# diagram.net
KiCad netlist of a schematic drawn in EAGLE
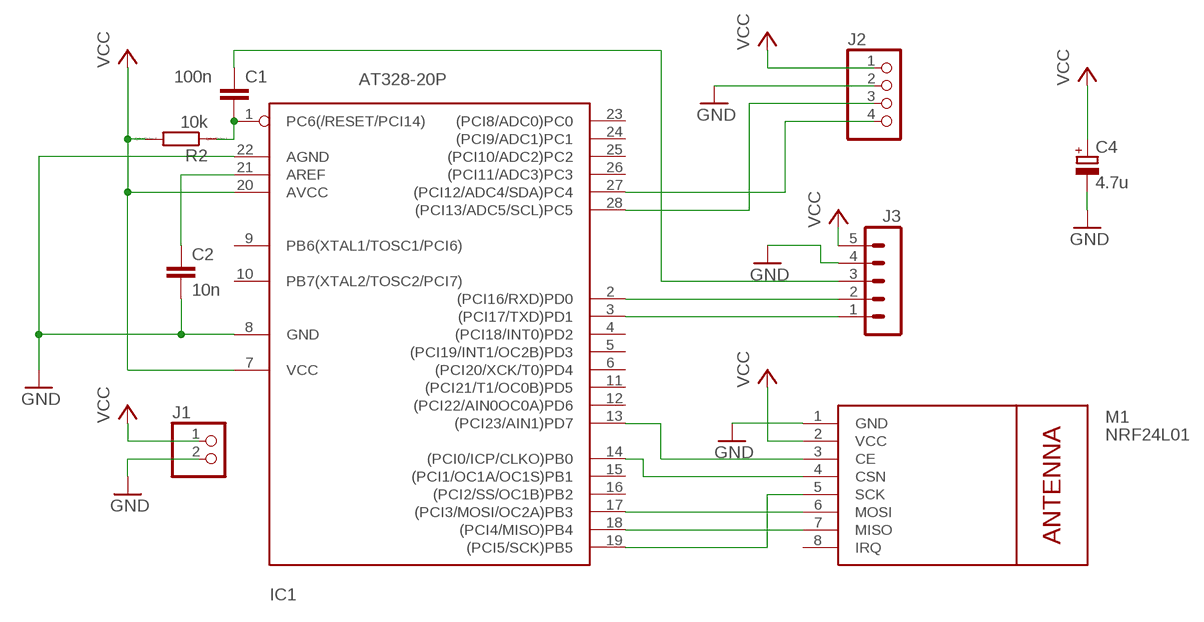
[diagram p0: schematic, sheet 1]

(export (version "E")
  (design (tool "Eeschema 10.0.6"))
  (components
    (comp (ref "C1")
      (value "100n")
      (footprint "eagle-import:C050-024X044")
      (libsource (lib "eagle-import") (part "C-EU050-024X044"))
    )
    (comp (ref "C2")
      (value "10n")
      (footprint "eagle-import:C050-024X044")
      (libsource (lib "eagle-import") (part "C-EU050-024X044"))
    )
    (comp (ref "C4")
      (value "4.7u")
      (footprint "eagle-import:E1,8-4")
      (libsource (lib "eagle-import") (part "CPOL-EUE1.8-4"))
    )
    (comp (ref "IC1")
      (value "AT328-20P")
      (footprint "eagle-import:DIL28-3")
      (libsource (lib "eagle-import") (part "ATMEGA328P-20"))
    )
    (comp (ref "J1")
      (value "PINHD-1X2")
      (footprint "eagle-import:1X02")
      (libsource (lib "eagle-import") (part "PINHD-1X2"))
    )
    (comp (ref "J2")
      (value "PINHD-1X4")
      (footprint "eagle-import:1X04")
      (libsource (lib "eagle-import") (part "PINHD-1X4"))
    )
    (comp (ref "J3")
      (value "MA05-1")
      (footprint "eagle-import:MA05-1")
      (libsource (lib "eagle-import") (part "MA05-1"))
    )
    (comp (ref "M1")
      (value "NRF24L01")
      (footprint "eagle-import:WIRELESS-NRF24L01")
      (libsource (lib "eagle-import") (part "WIRELESS-NRF24L01"))
    )
    (comp (ref "R2")
      (value "10k")
      (footprint "eagle-import:0204_7")
      (libsource (lib "eagle-import") (part "R0204/7"))
    )
  )
  (nets
    (net (code "1") (name "GND") (class "Default")
      (node (ref "C2") (pin "2") (pinfunction "2_2") (pintype "passive"))
      (node (ref "C4") (pin "-") (pinfunction "-_-") (pintype "passive"))
      (node (ref "IC1") (pin "22") (pinfunction "AGND_22") (pintype "bidirectional"))
      (node (ref "IC1") (pin "8") (pinfunction "GND_8") (pintype "bidirectional"))
      (node (ref "J1") (pin "2") (pinfunction "2_2") (pintype "passive"))
      (node (ref "J2") (pin "2") (pinfunction "2_2") (pintype "passive"))
      (node (ref "J3") (pin "4") (pinfunction "4_4") (pintype "passive"))
      (node (ref "M1") (pin "1") (pinfunction "GND_1") (pintype "power_in"))
    )
    (net (code "2") (name "Net-(C1-Pad1)") (class "Default")
      (node (ref "C1") (pin "1") (pinfunction "1_1") (pintype "passive"))
      (node (ref "J3") (pin "3") (pinfunction "3_3") (pintype "passive"))
    )
    (net (code "3") (name "Net-(IC1-(PCI0{slash}ICP{slash}CLKO)PB0)") (class "Default")
      (node (ref "IC1") (pin "14") (pinfunction "(PCI0/ICP/CLKO)PB0_14") (pintype "bidirectional"))
      (node (ref "M1") (pin "4") (pinfunction "CSN_4") (pintype "bidirectional"))
    )
    (net (code "4") (name "Net-(IC1-(PCI3{slash}MOSI{slash}OC2A)PB3)") (class "Default")
      (node (ref "IC1") (pin "17") (pinfunction "(PCI3/MOSI/OC2A)PB3_17") (pintype "bidirectional"))
      (node (ref "M1") (pin "6") (pinfunction "MOSI_6") (pintype "bidirectional"))
    )
    (net (code "5") (name "Net-(IC1-(PCI4{slash}MISO)PB4)") (class "Default")
      (node (ref "IC1") (pin "18") (pinfunction "(PCI4/MISO)PB4_18") (pintype "bidirectional"))
      (node (ref "M1") (pin "7") (pinfunction "MISO_7") (pintype "bidirectional"))
    )
    (net (code "6") (name "Net-(IC1-(PCI5{slash}SCK)PB5)") (class "Default")
      (node (ref "IC1") (pin "19") (pinfunction "(PCI5/SCK)PB5_19") (pintype "bidirectional"))
      (node (ref "M1") (pin "5") (pinfunction "SCK_5") (pintype "bidirectional"))
    )
    (net (code "7") (name "Net-(IC1-(PCI12{slash}ADC4{slash}SDA)PC4)") (class "Default")
      (node (ref "IC1") (pin "27") (pinfunction "(PCI12/ADC4/SDA)PC4_27") (pintype "bidirectional"))
      (node (ref "J2") (pin "4") (pinfunction "4_4") (pintype "passive"))
    )
    (net (code "8") (name "Net-(IC1-(PCI13{slash}ADC5{slash}SCL)PC5)") (class "Default")
      (node (ref "IC1") (pin "28") (pinfunction "(PCI13/ADC5/SCL)PC5_28") (pintype "bidirectional"))
      (node (ref "J2") (pin "3") (pinfunction "3_3") (pintype "passive"))
    )
    (net (code "9") (name "Net-(IC1-(PCI16{slash}RXD)PD0)") (class "Default")
      (node (ref "IC1") (pin "2") (pinfunction "(PCI16/RXD)PD0_2") (pintype "bidirectional"))
      (node (ref "J3") (pin "2") (pinfunction "2_2") (pintype "passive"))
    )
    (net (code "10") (name "Net-(IC1-(PCI17{slash}TXD)PD1)") (class "Default")
      (node (ref "IC1") (pin "3") (pinfunction "(PCI17/TXD)PD1_3") (pintype "bidirectional"))
      (node (ref "J3") (pin "1") (pinfunction "1_1") (pintype "passive"))
    )
    (net (code "11") (name "Net-(IC1-(PCI23{slash}AIN1)PD7)") (class "Default")
      (node (ref "IC1") (pin "13") (pinfunction "(PCI23/AIN1)PD7_13") (pintype "bidirectional"))
      (node (ref "M1") (pin "3") (pinfunction "CE_3") (pintype "bidirectional"))
    )
    (net (code "12") (name "Net-(IC1-AREF)") (class "Default")
      (node (ref "C2") (pin "1") (pinfunction "1_1") (pintype "passive"))
      (node (ref "IC1") (pin "21") (pinfunction "AREF_21") (pintype "bidirectional"))
    )
    (net (code "13") (name "Net-(IC1-PC6({slash}RESET{slash}PCI14))") (class "Default")
      (node (ref "C1") (pin "2") (pinfunction "2_2") (pintype "passive"))
      (node (ref "IC1") (pin "1") (pinfunction "PC6(/RESET/PCI14)_1") (pintype "bidirectional"))
      (node (ref "R2") (pin "1") (pinfunction "1_1") (pintype "passive"))
    )
    (net (code "14") (name "VCC") (class "Default")
      (node (ref "C4") (pin "+") (pinfunction "+_+") (pintype "passive"))
      (node (ref "IC1") (pin "20") (pinfunction "AVCC_20") (pintype "bidirectional"))
      (node (ref "IC1") (pin "7") (pinfunction "VCC_7") (pintype "bidirectional"))
      (node (ref "J1") (pin "1") (pinfunction "1_1") (pintype "passive"))
      (node (ref "J2") (pin "1") (pinfunction "1_1") (pintype "passive"))
      (node (ref "J3") (pin "5") (pinfunction "5_5") (pintype "passive"))
      (node (ref "M1") (pin "2") (pinfunction "VCC_2") (pintype "power_in"))
      (node (ref "R2") (pin "2") (pinfunction "2_2") (pintype "passive"))
    )
    (net (code "15") (name "unconnected-(IC1-(PCI1{slash}OC1A{slash}OC1S)PB1-Pad15)") (class "Default")
      (node (ref "IC1") (pin "15") (pinfunction "(PCI1/OC1A/OC1S)PB1_15") (pintype "bidirectional"))
    )
    (net (code "16") (name "unconnected-(IC1-(PCI2{slash}SS{slash}OC1B)PB2-Pad16)") (class "Default")
      (node (ref "IC1") (pin "16") (pinfunction "(PCI2/SS/OC1B)PB2_16") (pintype "bidirectional"))
    )
    (net (code "17") (name "unconnected-(IC1-(PCI8{slash}ADC0)PC0-Pad23)") (class "Default")
      (node (ref "IC1") (pin "23") (pinfunction "(PCI8/ADC0)PC0_23") (pintype "bidirectional"))
    )
    (net (code "18") (name "unconnected-(IC1-(PCI9{slash}ADC1)PC1-Pad24)") (class "Default")
      (node (ref "IC1") (pin "24") (pinfunction "(PCI9/ADC1)PC1_24") (pintype "bidirectional"))
    )
    (net (code "19") (name "unconnected-(IC1-(PCI10{slash}ADC2)PC2-Pad25)") (class "Default")
      (node (ref "IC1") (pin "25") (pinfunction "(PCI10/ADC2)PC2_25") (pintype "bidirectional"))
    )
    (net (code "20") (name "unconnected-(IC1-(PCI11{slash}ADC3)PC3-Pad26)") (class "Default")
      (node (ref "IC1") (pin "26") (pinfunction "(PCI11/ADC3)PC3_26") (pintype "bidirectional"))
    )
    (net (code "21") (name "unconnected-(IC1-(PCI18{slash}INT0)PD2-Pad4)") (class "Default")
      (node (ref "IC1") (pin "4") (pinfunction "(PCI18/INT0)PD2_4") (pintype "bidirectional"))
    )
    (net (code "22") (name "unconnected-(IC1-(PCI19{slash}INT1{slash}OC2B)PD3-Pad5)") (class "Default")
      (node (ref "IC1") (pin "5") (pinfunction "(PCI19/INT1/OC2B)PD3_5") (pintype "bidirectional"))
    )
    (net (code "23") (name "unconnected-(IC1-(PCI20{slash}XCK{slash}T0)PD4-Pad6)") (class "Default")
      (node (ref "IC1") (pin "6") (pinfunction "(PCI20/XCK/T0)PD4_6") (pintype "bidirectional"))
    )
    (net (code "24") (name "unconnected-(IC1-(PCI21{slash}T1{slash}OC0B)PD5-Pad11)") (class "Default")
      (node (ref "IC1") (pin "11") (pinfunction "(PCI21/T1/OC0B)PD5_11") (pintype "bidirectional"))
    )
    (net (code "25") (name "unconnected-(IC1-(PCI22{slash}AIN0OC0A)PD6-Pad12)") (class "Default")
      (node (ref "IC1") (pin "12") (pinfunction "(PCI22/AIN0OC0A)PD6_12") (pintype "bidirectional"))
    )
    (net (code "26") (name "unconnected-(IC1-PB6(XTAL1{slash}TOSC1{slash}PCI6)-Pad9)") (class "Default")
      (node (ref "IC1") (pin "9") (pinfunction "PB6(XTAL1/TOSC1/PCI6)_9") (pintype "bidirectional"))
    )
    (net (code "27") (name "unconnected-(IC1-PB7(XTAL2{slash}TOSC2{slash}PCI7)-Pad10)") (class "Default")
      (node (ref "IC1") (pin "10") (pinfunction "PB7(XTAL2/TOSC2/PCI7)_10") (pintype "bidirectional"))
    )
    (net (code "28") (name "unconnected-(M1-IRQ-Pad8)") (class "Default")
      (node (ref "M1") (pin "8") (pinfunction "IRQ_8") (pintype "bidirectional"))
    )
  )
)
